# AmbaSat-04-OPT3001.net
KiCad netlist of a schematic drawn in EAGLE
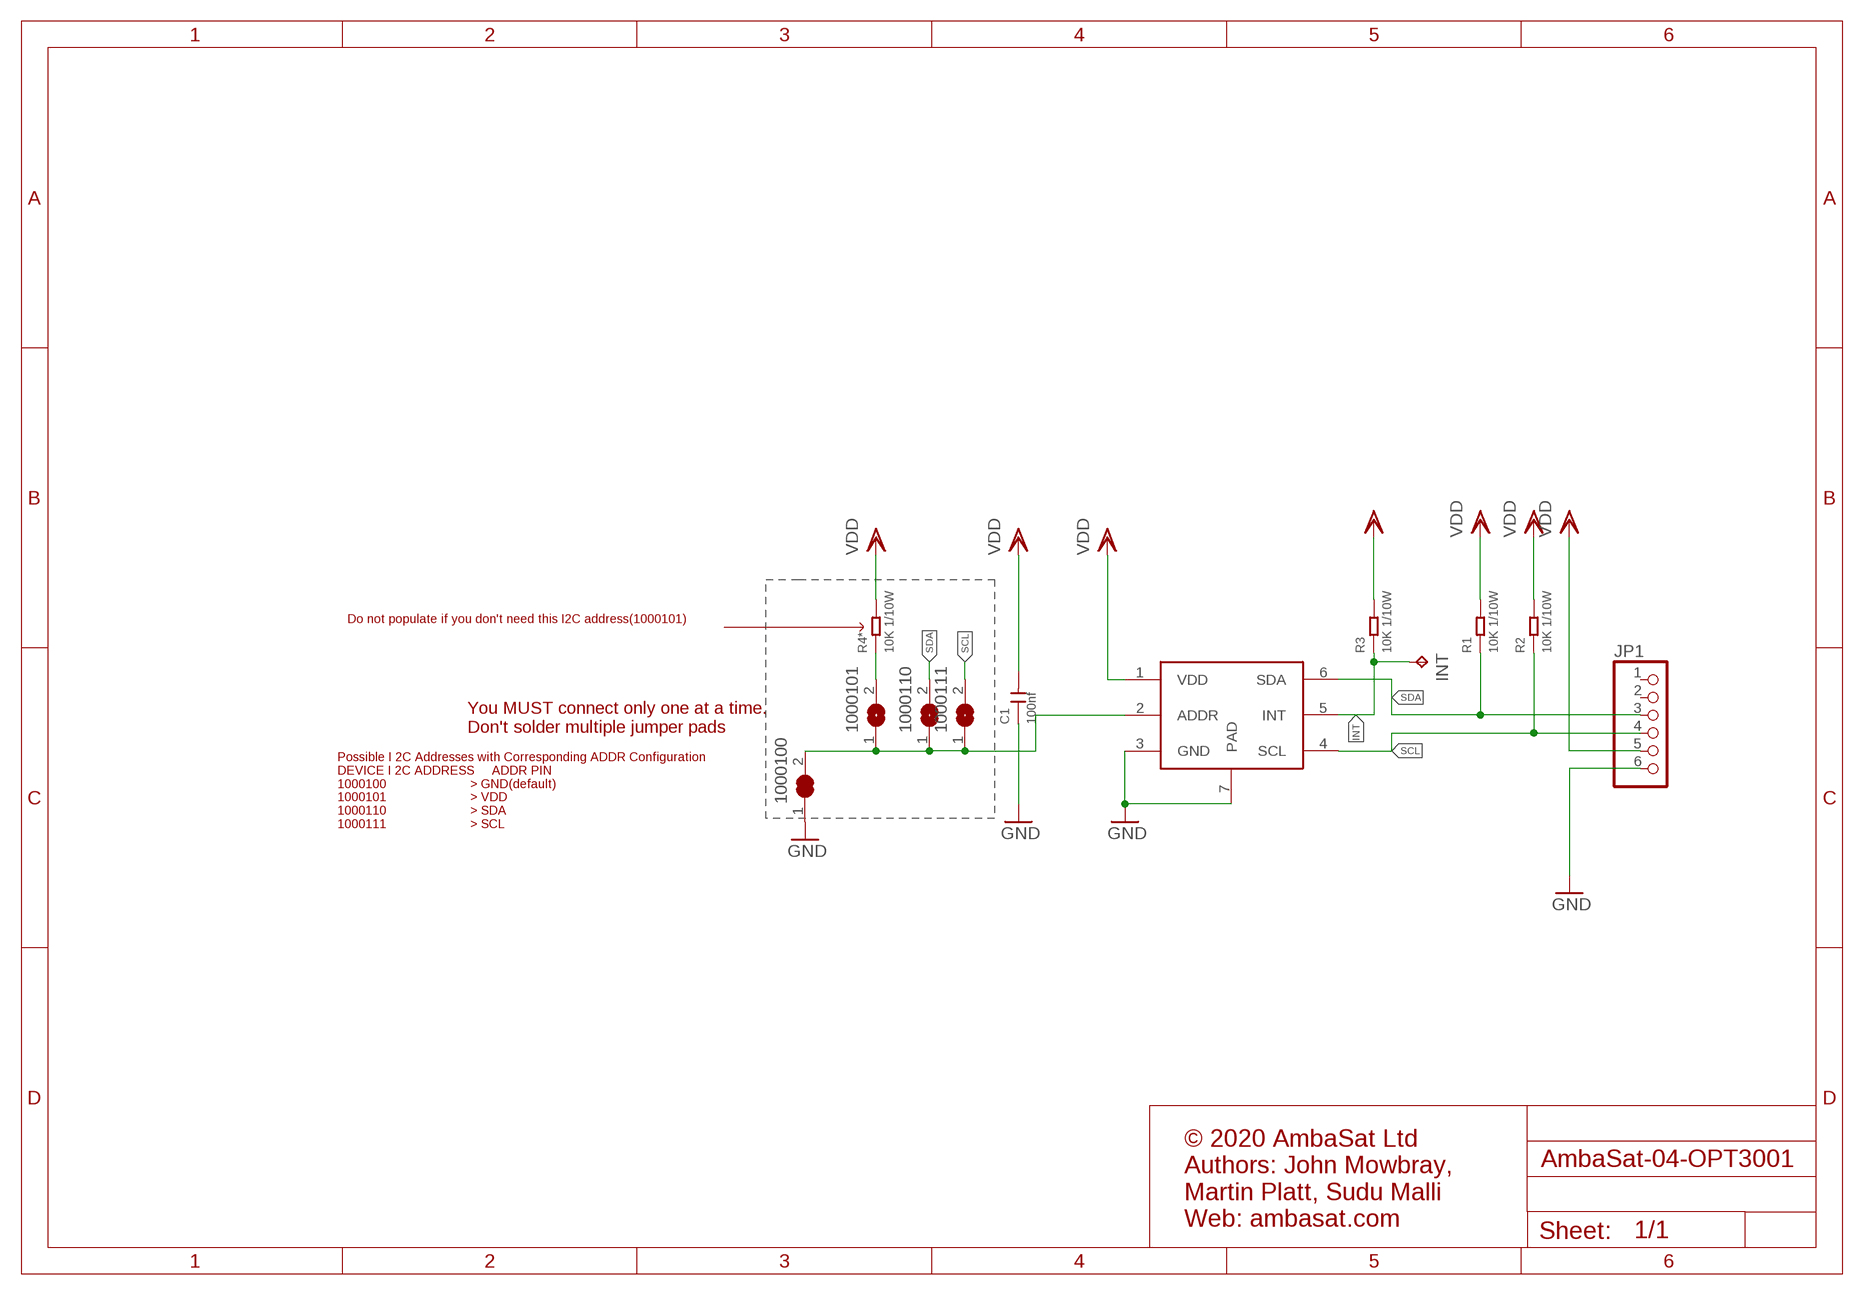
[diagram p0: schematic, sheet 1]

(export (version "E")
  (design (tool "Eeschema 10.0.6"))
  (components
    (comp (ref "1000100")
      (value "SOLDERJUMPER_CLOSED")
      (footprint "eagle-import:SOLDERJUMPER_CLOSEDWIRE")
      (libsource (lib "eagle-import") (part "SOLDERJUMPER_CLOSED"))
    )
    (comp (ref "1000101")
      (value "SJ")
      (footprint "eagle-import:SJ")
      (libsource (lib "eagle-import") (part "SJ"))
    )
    (comp (ref "1000110")
      (value "SJ")
      (footprint "eagle-import:SJ")
      (libsource (lib "eagle-import") (part "SJ"))
    )
    (comp (ref "1000111")
      (value "SJ")
      (footprint "eagle-import:SJ")
      (libsource (lib "eagle-import") (part "SJ"))
    )
    (comp (ref "C1")
      (value "100nf")
      (footprint "eagle-import:C0603")
      (fields (field (name "MPN") "CC0603KRX7R9BB104"))
      (libsource (lib "eagle-import") (part "CERAMIC-100NF-50V-10%-X7R(0603)"))
    )
    (comp (ref "INT")
      (value "TPTP11R")
      (footprint "eagle-import:TP11R")
      (libsource (lib "eagle-import") (part "TPTP11R"))
    )
    (comp (ref "JP1")
      (value "HEADER-1X6")
      (footprint "eagle-import:1X06_OVAL")
      (libsource (lib "eagle-import") (part "HEADER-1X6"))
    )
    (comp (ref "R1")
      (value "10K 1/10W")
      (footprint "eagle-import:R0603")
      (fields (field (name "MPN") "RC0603JR-0710KL"))
      (libsource (lib "eagle-import") (part "SMD-RES-10K-5%-1/10W(0603)"))
    )
    (comp (ref "R2")
      (value "10K 1/10W")
      (footprint "eagle-import:R0603")
      (fields (field (name "MPN") "RC0603JR-0710KL"))
      (libsource (lib "eagle-import") (part "SMD-RES-10K-5%-1/10W(0603)"))
    )
    (comp (ref "R3")
      (value "10K 1/10W")
      (footprint "eagle-import:R0603")
      (fields (field (name "MPN") "RC0603JR-0710KL"))
      (libsource (lib "eagle-import") (part "SMD-RES-10K-5%-1/10W(0603)"))
    )
    (comp (ref "R4*")
      (value "10K 1/10W")
      (footprint "eagle-import:R0603")
      (fields (field (name "MPN") "RC0603JR-0710KL"))
      (libsource (lib "eagle-import") (part "SMD-RES-10K-5%-1/10W(0603)"))
    )
    (comp (ref "U2")
      (value "OPT3001")
      (footprint "eagle-import:SON65P200X200X65-7N")
      (fields (field (name "MPN") "OPT3001DNPT"))
      (libsource (lib "eagle-import") (part "OPT3001"))
    )
  )
  (nets
    (net (code "1") (name "GND") (class "Default")
      (node (ref "1000100") (pin "1") (pinfunction "1_1") (pintype "passive"))
      (node (ref "C1") (pin "1") (pinfunction "1_1") (pintype "passive"))
      (node (ref "JP1") (pin "6") (pinfunction "6_6") (pintype "passive"))
      (node (ref "U2") (pin "3") (pinfunction "GND_3") (pintype "bidirectional"))
      (node (ref "U2") (pin "7") (pinfunction "PAD_7") (pintype "bidirectional"))
    )
    (net (code "2") (name "INT") (class "Default")
      (node (ref "INT") (pin "TP") (pinfunction "TP_TP") (pintype "input"))
      (node (ref "R3") (pin "1") (pinfunction "1_1") (pintype "passive"))
      (node (ref "U2") (pin "5") (pinfunction "INT_5") (pintype "bidirectional"))
    )
    (net (code "3") (name "Net-(1000101-Pad2)") (class "Default")
      (node (ref "1000101") (pin "2") (pinfunction "2_2") (pintype "passive"))
      (node (ref "R4*") (pin "1") (pinfunction "1_1") (pintype "passive"))
    )
    (net (code "4") (name "Net-(U2-ADDR)") (class "Default")
      (node (ref "1000100") (pin "2") (pinfunction "2_2") (pintype "passive"))
      (node (ref "1000101") (pin "1") (pinfunction "1_1") (pintype "passive"))
      (node (ref "1000110") (pin "1") (pinfunction "1_1") (pintype "passive"))
      (node (ref "1000111") (pin "1") (pinfunction "1_1") (pintype "passive"))
      (node (ref "U2") (pin "2") (pinfunction "ADDR_2") (pintype "bidirectional"))
    )
    (net (code "5") (name "SCL") (class "Default")
      (node (ref "1000111") (pin "2") (pinfunction "2_2") (pintype "passive"))
      (node (ref "JP1") (pin "4") (pinfunction "4_4") (pintype "passive"))
      (node (ref "R2") (pin "1") (pinfunction "1_1") (pintype "passive"))
      (node (ref "U2") (pin "4") (pinfunction "SCL_4") (pintype "bidirectional"))
    )
    (net (code "6") (name "SDA") (class "Default")
      (node (ref "1000110") (pin "2") (pinfunction "2_2") (pintype "passive"))
      (node (ref "JP1") (pin "3") (pinfunction "3_3") (pintype "passive"))
      (node (ref "R1") (pin "1") (pinfunction "1_1") (pintype "passive"))
      (node (ref "U2") (pin "6") (pinfunction "SDA_6") (pintype "bidirectional"))
    )
    (net (code "7") (name "VDD") (class "Default")
      (node (ref "C1") (pin "2") (pinfunction "2_2") (pintype "passive"))
      (node (ref "JP1") (pin "5") (pinfunction "5_5") (pintype "passive"))
      (node (ref "R1") (pin "2") (pinfunction "2_2") (pintype "passive"))
      (node (ref "R2") (pin "2") (pinfunction "2_2") (pintype "passive"))
      (node (ref "R3") (pin "2") (pinfunction "2_2") (pintype "passive"))
      (node (ref "R4*") (pin "2") (pinfunction "2_2") (pintype "passive"))
      (node (ref "U2") (pin "1") (pinfunction "VDD_1") (pintype "bidirectional"))
    )
    (net (code "8") (name "unconnected-(JP1-Pad1)") (class "Default")
      (node (ref "JP1") (pin "1") (pinfunction "1_1") (pintype "passive"))
    )
    (net (code "9") (name "unconnected-(JP1-Pad2)") (class "Default")
      (node (ref "JP1") (pin "2") (pinfunction "2_2") (pintype "passive"))
    )
  )
)
